# TMC2209_Circuit_v11.net
KiCad netlist of a schematic drawn in EAGLE
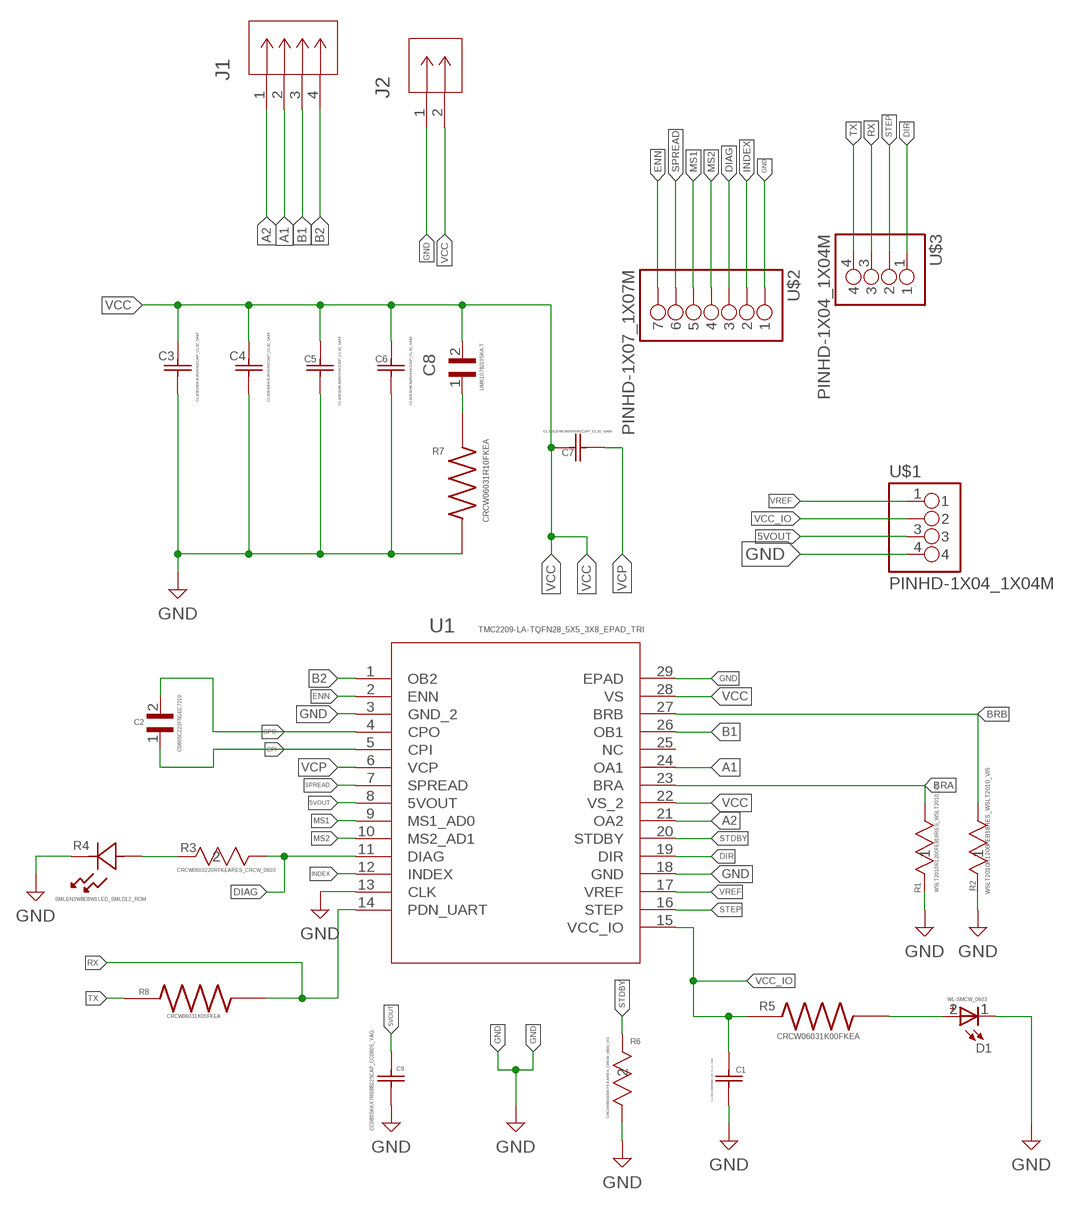
[diagram p0: schematic, sheet 1]

(export (version "E")
  (design (tool "Eeschema 10.0.6"))
  (components
    (comp (ref "C1")
      (value "CL10B104KB8NNNCCAP_CL10_SAM")
      (footprint "eagle-import:CAP_CL10_SAM")
      (fields
        (field (name "MANUFACTURER_PART_NUMBER") "CL10B104KB8NNNC")
        (field (name "COPYRIGHT") "Copyright (C) 2025 Ultra Librarian. All rights reserved.")
      )
      (libsource (lib "eagle-import") (part "CL10B104KB8NNNCCAP_CL10_SAM"))
    )
    (comp (ref "C2")
      (value "C0805C223F5GEC7210")
      (footprint "eagle-import:CAPC2012X120N")
      (libsource (lib "eagle-import") (part "C0805C223F5GEC7210"))
    )
    (comp (ref "C3")
      (value "CL32B106KBJNNNECAP_CL32_SAM")
      (footprint "eagle-import:CAP_CL32_SAM")
      (fields
        (field (name "MANUFACTURER_PART_NUMBER") "CL32B106KBJNNNE")
        (field (name "COPYRIGHT") "Copyright (C) 2025 Ultra Librarian. All rights reserved.")
      )
      (libsource (lib "eagle-import") (part "CL32B106KBJNNNECAP_CL32_SAM"))
    )
    (comp (ref "C4")
      (value "CL32B106KBJNNNECAP_CL32_SAM")
      (footprint "eagle-import:CAP_CL32_SAM")
      (fields
        (field (name "MANUFACTURER_PART_NUMBER") "CL32B106KBJNNNE")
        (field (name "COPYRIGHT") "Copyright (C) 2025 Ultra Librarian. All rights reserved.")
      )
      (libsource (lib "eagle-import") (part "CL32B106KBJNNNECAP_CL32_SAM"))
    )
    (comp (ref "C5")
      (value "CL10B104KB8NNNCCAP_CL10_SAM")
      (footprint "eagle-import:CAP_CL10_SAM")
      (fields
        (field (name "MANUFACTURER_PART_NUMBER") "CL10B104KB8NNNC")
        (field (name "COPYRIGHT") "Copyright (C) 2025 Ultra Librarian. All rights reserved.")
      )
      (libsource (lib "eagle-import") (part "CL10B104KB8NNNCCAP_CL10_SAM"))
    )
    (comp (ref "C6")
      (value "CL10B104KB8NNNCCAP_CL10_SAM")
      (footprint "eagle-import:CAP_CL10_SAM")
      (fields
        (field (name "MANUFACTURER_PART_NUMBER") "CL10B104KB8NNNC")
        (field (name "COPYRIGHT") "Copyright (C) 2025 Ultra Librarian. All rights reserved.")
      )
      (libsource (lib "eagle-import") (part "CL10B104KB8NNNCCAP_CL10_SAM"))
    )
    (comp (ref "C7")
      (value "CL10B104KB8NNNCCAP_CL10_SAM")
      (footprint "eagle-import:CAP_CL10_SAM")
      (fields
        (field (name "MANUFACTURER_PART_NUMBER") "CL10B104KB8NNNC")
        (field (name "COPYRIGHT") "Copyright (C) 2025 Ultra Librarian. All rights reserved.")
      )
      (libsource (lib "eagle-import") (part "CL10B104KB8NNNCCAP_CL10_SAM"))
    )
    (comp (ref "C8")
      (value "UMK107BJ105KA-T")
      (footprint "eagle-import:CAPC1608X90N")
      (libsource (lib "eagle-import") (part "UMK107BJ105KA-T"))
    )
    (comp (ref "C9")
      (value "CC0805KKX7R9BB225CAP_CC0805_YAG")
      (footprint "eagle-import:CAP_CC0805_YAG")
      (fields
        (field (name "MANUFACTURER_PART_NUMBER") "CC0805KKX7R9BB225")
        (field (name "COPYRIGHT") "Copyright (C) 2025 Ultra Librarian. All rights reserved.")
      )
      (libsource (lib "eagle-import") (part "CC0805KKX7R9BB225CAP_CC0805_YAG"))
    )
    (comp (ref "D1")
      (value "WL-SMCW_0603")
      (footprint "eagle-import:WL-SMCW_0603")
      (libsource (lib "eagle-import") (part "WL-SMCW_0603"))
    )
    (comp (ref "J1")
      (value "S4B-XH-A(LF)(SN)CONN_S4B-XH-A(LF)(SN)_JST")
      (footprint "eagle-import:CONN_S4B-XH-A(LF)(SN)_JST")
      (fields
        (field (name "MANUFACTURER_PART_NUMBER") "S4B-XH-A(LF)(SN)")
        (field (name "COPYRIGHT") "Copyright (C) 2025 Ultra Librarian. All rights reserved.")
      )
      (libsource (lib "eagle-import") (part "S4B-XH-A(LF)(SN)CONN_S4B-XH-A(LF)(SN)_JST"))
    )
    (comp (ref "J2")
      (value "S2B-PH-K-S(LF)(SN)CONN_S2B-PH-K-S_JST")
      (footprint "eagle-import:CONN_S2B-PH-K-S_JST")
      (fields
        (field (name "MANUFACTURER_PART_NUMBER") "S2B-PH-K-S(LF)(SN)")
        (field (name "COPYRIGHT") "Copyright (C) 2025 Ultra Librarian. All rights reserved.")
      )
      (libsource (lib "eagle-import") (part "S2B-PH-K-S(LF)(SN)CONN_S2B-PH-K-S_JST"))
    )
    (comp (ref "R1")
      (value "WSLT2010R1200FEB18RES_WSLT2010_VIS")
      (footprint "eagle-import:RES_WSLT2010_VIS")
      (fields
        (field (name "MANUFACTURER_PART_NUMBER") "WSLT2010R1200FEB18")
        (field (name "COPYRIGHT") "Copyright (C) 2025 Ultra Librarian. All rights reserved.")
      )
      (libsource (lib "eagle-import") (part "WSLT2010R1200FEB18RES_WSLT2010_VIS"))
    )
    (comp (ref "R2")
      (value "WSLT2010R1200FEB18RES_WSLT2010_VIS")
      (footprint "eagle-import:RES_WSLT2010_VIS")
      (fields
        (field (name "MANUFACTURER_PART_NUMBER") "WSLT2010R1200FEB18")
        (field (name "COPYRIGHT") "Copyright (C) 2025 Ultra Librarian. All rights reserved.")
      )
      (libsource (lib "eagle-import") (part "WSLT2010R1200FEB18RES_WSLT2010_VIS"))
    )
    (comp (ref "R3")
      (value "CRCW0603220RFKEARES_CRCW_0603")
      (footprint "eagle-import:RES_CRCW_0603")
      (fields
        (field (name "MANUFACTURER_PART_NUMBER") "CRCW0603220RFKEA")
        (field (name "COPYRIGHT") "Copyright (C) 2025 Ultra Librarian. All rights reserved.")
      )
      (libsource (lib "eagle-import") (part "CRCW0603220RFKEARES_CRCW_0603"))
    )
    (comp (ref "R4")
      (value "SMLEN3WBC8W1LED_SMLD12_ROM")
      (footprint "eagle-import:LED_SMLD12_ROM")
      (fields
        (field (name "MANUFACTURER_PART_NUMBER") "SMLEN3WBC8W1")
        (field (name "COPYRIGHT") "Copyright (C) 2025 Ultra Librarian. All rights reserved.")
      )
      (libsource (lib "eagle-import") (part "SMLEN3WBC8W1LED_SMLD12_ROM"))
    )
    (comp (ref "R5")
      (value "CRCW06031K00FKEA")
      (footprint "eagle-import:RESC1508X50N")
      (libsource (lib "eagle-import") (part "CRCW06031K00FKEA"))
    )
    (comp (ref "R6")
      (value "CRCW0603100KFKEARES_CRCW_0603_VIS")
      (footprint "eagle-import:RES_CRCW_0603_VIS")
      (fields
        (field (name "MANUFACTURER_PART_NUMBER") "CRCW0603100KFKEA")
        (field (name "COPYRIGHT") "Copyright (C) 2025 Ultra Librarian. All rights reserved.")
      )
      (libsource (lib "eagle-import") (part "CRCW0603100KFKEARES_CRCW_0603_VIS"))
    )
    (comp (ref "R7")
      (value "CRCW06031R10FKEA")
      (footprint "eagle-import:RESC1508X50N")
      (libsource (lib "eagle-import") (part "CRCW06031R10FKEA"))
    )
    (comp (ref "R8")
      (value "CRCW06031K00FKEA")
      (footprint "eagle-import:RESC1508X50N")
      (libsource (lib "eagle-import") (part "CRCW06031K00FKEA"))
    )
    (comp (ref "U$1")
      (value "PINHD-1X04_1X04M")
      (footprint "eagle-import:1X04")
      (libsource (lib "eagle-import") (part "PINHD-1X04_1X04M"))
    )
    (comp (ref "U$2")
      (value "PINHD-1X07_1X07M")
      (footprint "eagle-import:1X07")
      (libsource (lib "eagle-import") (part "PINHD-1X07_1X07M"))
    )
    (comp (ref "U$3")
      (value "PINHD-1X04_1X04M")
      (footprint "eagle-import:1X04")
      (libsource (lib "eagle-import") (part "PINHD-1X04_1X04M"))
    )
    (comp (ref "U1")
      (value "TMC2209-LA-TQFN28_5X5_3X8_EPAD_TRI")
      (footprint "eagle-import:QFN28_5X5_3X8_EPAD_TRI")
      (fields
        (field (name "MANUFACTURER_PART_NUMBER") "TMC2209-LA-T")
        (field (name "COPYRIGHT") "Copyright (C) 2025 Ultra Librarian. All rights reserved.")
      )
      (libsource (lib "eagle-import") (part "TMC2209-LA-TQFN28_5X5_3X8_EPAD_TRI"))
    )
  )
  (nets
    (net (code "1") (name "5VOUT") (class "Default")
      (node (ref "C9") (pin "1") (pinfunction "1_1") (pintype "passive"))
      (node (ref "U$1") (pin "3") (pinfunction "3_3") (pintype "bidirectional"))
      (node (ref "U1") (pin "8") (pinfunction "5VOUT_8") (pintype "output"))
    )
    (net (code "2") (name "A1") (class "Default")
      (node (ref "J1") (pin "2") (pinfunction "2_2") (pintype "passive"))
      (node (ref "U1") (pin "24") (pinfunction "OA1_24") (pintype "output"))
    )
    (net (code "3") (name "A2") (class "Default")
      (node (ref "J1") (pin "1") (pinfunction "1_1") (pintype "passive"))
      (node (ref "U1") (pin "21") (pinfunction "OA2_21") (pintype "output"))
    )
    (net (code "4") (name "B1") (class "Default")
      (node (ref "J1") (pin "3") (pinfunction "3_3") (pintype "passive"))
      (node (ref "U1") (pin "26") (pinfunction "OB1_26") (pintype "output"))
    )
    (net (code "5") (name "B2") (class "Default")
      (node (ref "J1") (pin "4") (pinfunction "4_4") (pintype "passive"))
      (node (ref "U1") (pin "1") (pinfunction "OB2_1") (pintype "output"))
    )
    (net (code "6") (name "BRA") (class "Default")
      (node (ref "R1") (pin "2") (pinfunction "2_2") (pintype "passive"))
      (node (ref "U1") (pin "23") (pinfunction "BRA_23") (pintype "passive"))
    )
    (net (code "7") (name "BRB") (class "Default")
      (node (ref "R2") (pin "2") (pinfunction "2_2") (pintype "passive"))
      (node (ref "U1") (pin "27") (pinfunction "BRB_27") (pintype "passive"))
    )
    (net (code "8") (name "CPI") (class "Default")
      (node (ref "C2") (pin "1") (pinfunction "1_1") (pintype "passive"))
      (node (ref "U1") (pin "5") (pinfunction "CPI_5") (pintype "input"))
    )
    (net (code "9") (name "CPO") (class "Default")
      (node (ref "C2") (pin "2") (pinfunction "2_2") (pintype "passive"))
      (node (ref "U1") (pin "4") (pinfunction "CPO_4") (pintype "output"))
    )
    (net (code "10") (name "DIAG") (class "Default")
      (node (ref "R3") (pin "1") (pinfunction "1_1") (pintype "passive"))
      (node (ref "U$2") (pin "3") (pinfunction "3_3") (pintype "bidirectional"))
      (node (ref "U1") (pin "11") (pinfunction "DIAG_11") (pintype "output"))
    )
    (net (code "11") (name "DIR") (class "Default")
      (node (ref "U$3") (pin "1") (pinfunction "1_1") (pintype "bidirectional"))
      (node (ref "U1") (pin "19") (pinfunction "DIR_19") (pintype "input"))
    )
    (net (code "12") (name "ENN") (class "Default")
      (node (ref "U$2") (pin "7") (pinfunction "7_7") (pintype "bidirectional"))
      (node (ref "U1") (pin "2") (pinfunction "ENN_2") (pintype "input"))
    )
    (net (code "13") (name "GND") (class "Default")
      (node (ref "C1") (pin "2") (pinfunction "2_2") (pintype "passive"))
      (node (ref "C3") (pin "1") (pinfunction "1_1") (pintype "passive"))
      (node (ref "C4") (pin "1") (pinfunction "1_1") (pintype "passive"))
      (node (ref "C5") (pin "1") (pinfunction "1_1") (pintype "passive"))
      (node (ref "C6") (pin "1") (pinfunction "1_1") (pintype "passive"))
      (node (ref "C9") (pin "2") (pinfunction "2_2") (pintype "passive"))
      (node (ref "D1") (pin "1") (pinfunction "-_1") (pintype "passive"))
      (node (ref "J2") (pin "1") (pinfunction "1_1") (pintype "passive"))
      (node (ref "R1") (pin "1") (pinfunction "1_1") (pintype "passive"))
      (node (ref "R2") (pin "1") (pinfunction "1_1") (pintype "passive"))
      (node (ref "R4") (pin "1") (pinfunction "1_1") (pintype "passive"))
      (node (ref "R6") (pin "1") (pinfunction "1_1") (pintype "passive"))
      (node (ref "R7") (pin "1") (pinfunction "1_1") (pintype "passive"))
      (node (ref "U$1") (pin "4") (pinfunction "4_4") (pintype "bidirectional"))
      (node (ref "U$2") (pin "1") (pinfunction "1_1") (pintype "bidirectional"))
      (node (ref "U1") (pin "13") (pinfunction "CLK_13") (pintype "input"))
      (node (ref "U1") (pin "18") (pinfunction "GND_18") (pintype "power_in"))
      (node (ref "U1") (pin "29") (pinfunction "EPAD_29") (pintype "passive"))
      (node (ref "U1") (pin "3") (pinfunction "GND_2_3") (pintype "power_in"))
    )
    (net (code "14") (name "INDEX") (class "Default")
      (node (ref "U$2") (pin "2") (pinfunction "2_2") (pintype "bidirectional"))
      (node (ref "U1") (pin "12") (pinfunction "INDEX_12") (pintype "output"))
    )
    (net (code "15") (name "MS1") (class "Default")
      (node (ref "U$2") (pin "5") (pinfunction "5_5") (pintype "bidirectional"))
      (node (ref "U1") (pin "9") (pinfunction "MS1_AD0_9") (pintype "input"))
    )
    (net (code "16") (name "MS2") (class "Default")
      (node (ref "U$2") (pin "4") (pinfunction "4_4") (pintype "bidirectional"))
      (node (ref "U1") (pin "10") (pinfunction "MS2_AD1_10") (pintype "input"))
    )
    (net (code "17") (name "Net-(C8-Pad1)") (class "Default")
      (node (ref "C8") (pin "1") (pinfunction "1_1") (pintype "passive"))
      (node (ref "R7") (pin "2") (pinfunction "2_2") (pintype "passive"))
    )
    (net (code "18") (name "Net-(D1-+)") (class "Default")
      (node (ref "D1") (pin "2") (pinfunction "+_2") (pintype "passive"))
      (node (ref "R5") (pin "2") (pinfunction "2_2") (pintype "passive"))
    )
    (net (code "19") (name "Net-(R3-Pad2)") (class "Default")
      (node (ref "R3") (pin "2") (pinfunction "2_2") (pintype "passive"))
      (node (ref "R4") (pin "2") (pinfunction "2_2") (pintype "passive"))
    )
    (net (code "20") (name "RX") (class "Default")
      (node (ref "R8") (pin "2") (pinfunction "2_2") (pintype "passive"))
      (node (ref "U$3") (pin "3") (pinfunction "3_3") (pintype "bidirectional"))
      (node (ref "U1") (pin "14") (pinfunction "PDN_UART_14") (pintype "bidirectional"))
    )
    (net (code "21") (name "SPREAD") (class "Default")
      (node (ref "U$2") (pin "6") (pinfunction "6_6") (pintype "bidirectional"))
      (node (ref "U1") (pin "7") (pinfunction "SPREAD_7") (pintype "input"))
    )
    (net (code "22") (name "STDBY") (class "Default")
      (node (ref "R6") (pin "2") (pinfunction "2_2") (pintype "passive"))
      (node (ref "U1") (pin "20") (pinfunction "STDBY_20") (pintype "input"))
    )
    (net (code "23") (name "STEP") (class "Default")
      (node (ref "U$3") (pin "2") (pinfunction "2_2") (pintype "bidirectional"))
      (node (ref "U1") (pin "16") (pinfunction "STEP_16") (pintype "input"))
    )
    (net (code "24") (name "TX") (class "Default")
      (node (ref "R8") (pin "1") (pinfunction "1_1") (pintype "passive"))
      (node (ref "U$3") (pin "4") (pinfunction "4_4") (pintype "bidirectional"))
    )
    (net (code "25") (name "VCC") (class "Default")
      (node (ref "C3") (pin "2") (pinfunction "2_2") (pintype "passive"))
      (node (ref "C4") (pin "2") (pinfunction "2_2") (pintype "passive"))
      (node (ref "C5") (pin "2") (pinfunction "2_2") (pintype "passive"))
      (node (ref "C6") (pin "2") (pinfunction "2_2") (pintype "passive"))
      (node (ref "C7") (pin "2") (pinfunction "2_2") (pintype "passive"))
      (node (ref "C8") (pin "2") (pinfunction "2_2") (pintype "passive"))
      (node (ref "J2") (pin "2") (pinfunction "2_2") (pintype "passive"))
      (node (ref "U1") (pin "22") (pinfunction "VS_2_22") (pintype "power_in"))
      (node (ref "U1") (pin "28") (pinfunction "VS_28") (pintype "power_in"))
    )
    (net (code "26") (name "VCC_IO") (class "Default")
      (node (ref "C1") (pin "1") (pinfunction "1_1") (pintype "passive"))
      (node (ref "R5") (pin "1") (pinfunction "1_1") (pintype "passive"))
      (node (ref "U$1") (pin "2") (pinfunction "2_2") (pintype "bidirectional"))
      (node (ref "U1") (pin "15") (pinfunction "VCC_IO_15") (pintype "power_in"))
    )
    (net (code "27") (name "VCP") (class "Default")
      (node (ref "C7") (pin "1") (pinfunction "1_1") (pintype "passive"))
      (node (ref "U1") (pin "6") (pinfunction "VCP_6") (pintype "power_in"))
    )
    (net (code "28") (name "VREF") (class "Default")
      (node (ref "U$1") (pin "1") (pinfunction "1_1") (pintype "bidirectional"))
      (node (ref "U1") (pin "17") (pinfunction "VREF_17") (pintype "input"))
    )
    (net (code "29") (name "unconnected-(U1-NC-Pad25)") (class "Default")
      (node (ref "U1") (pin "25") (pinfunction "NC_25") (pintype "no_connect"))
    )
  )
)
